# nosecone.net
KiCad netlist of a schematic drawn in EAGLE
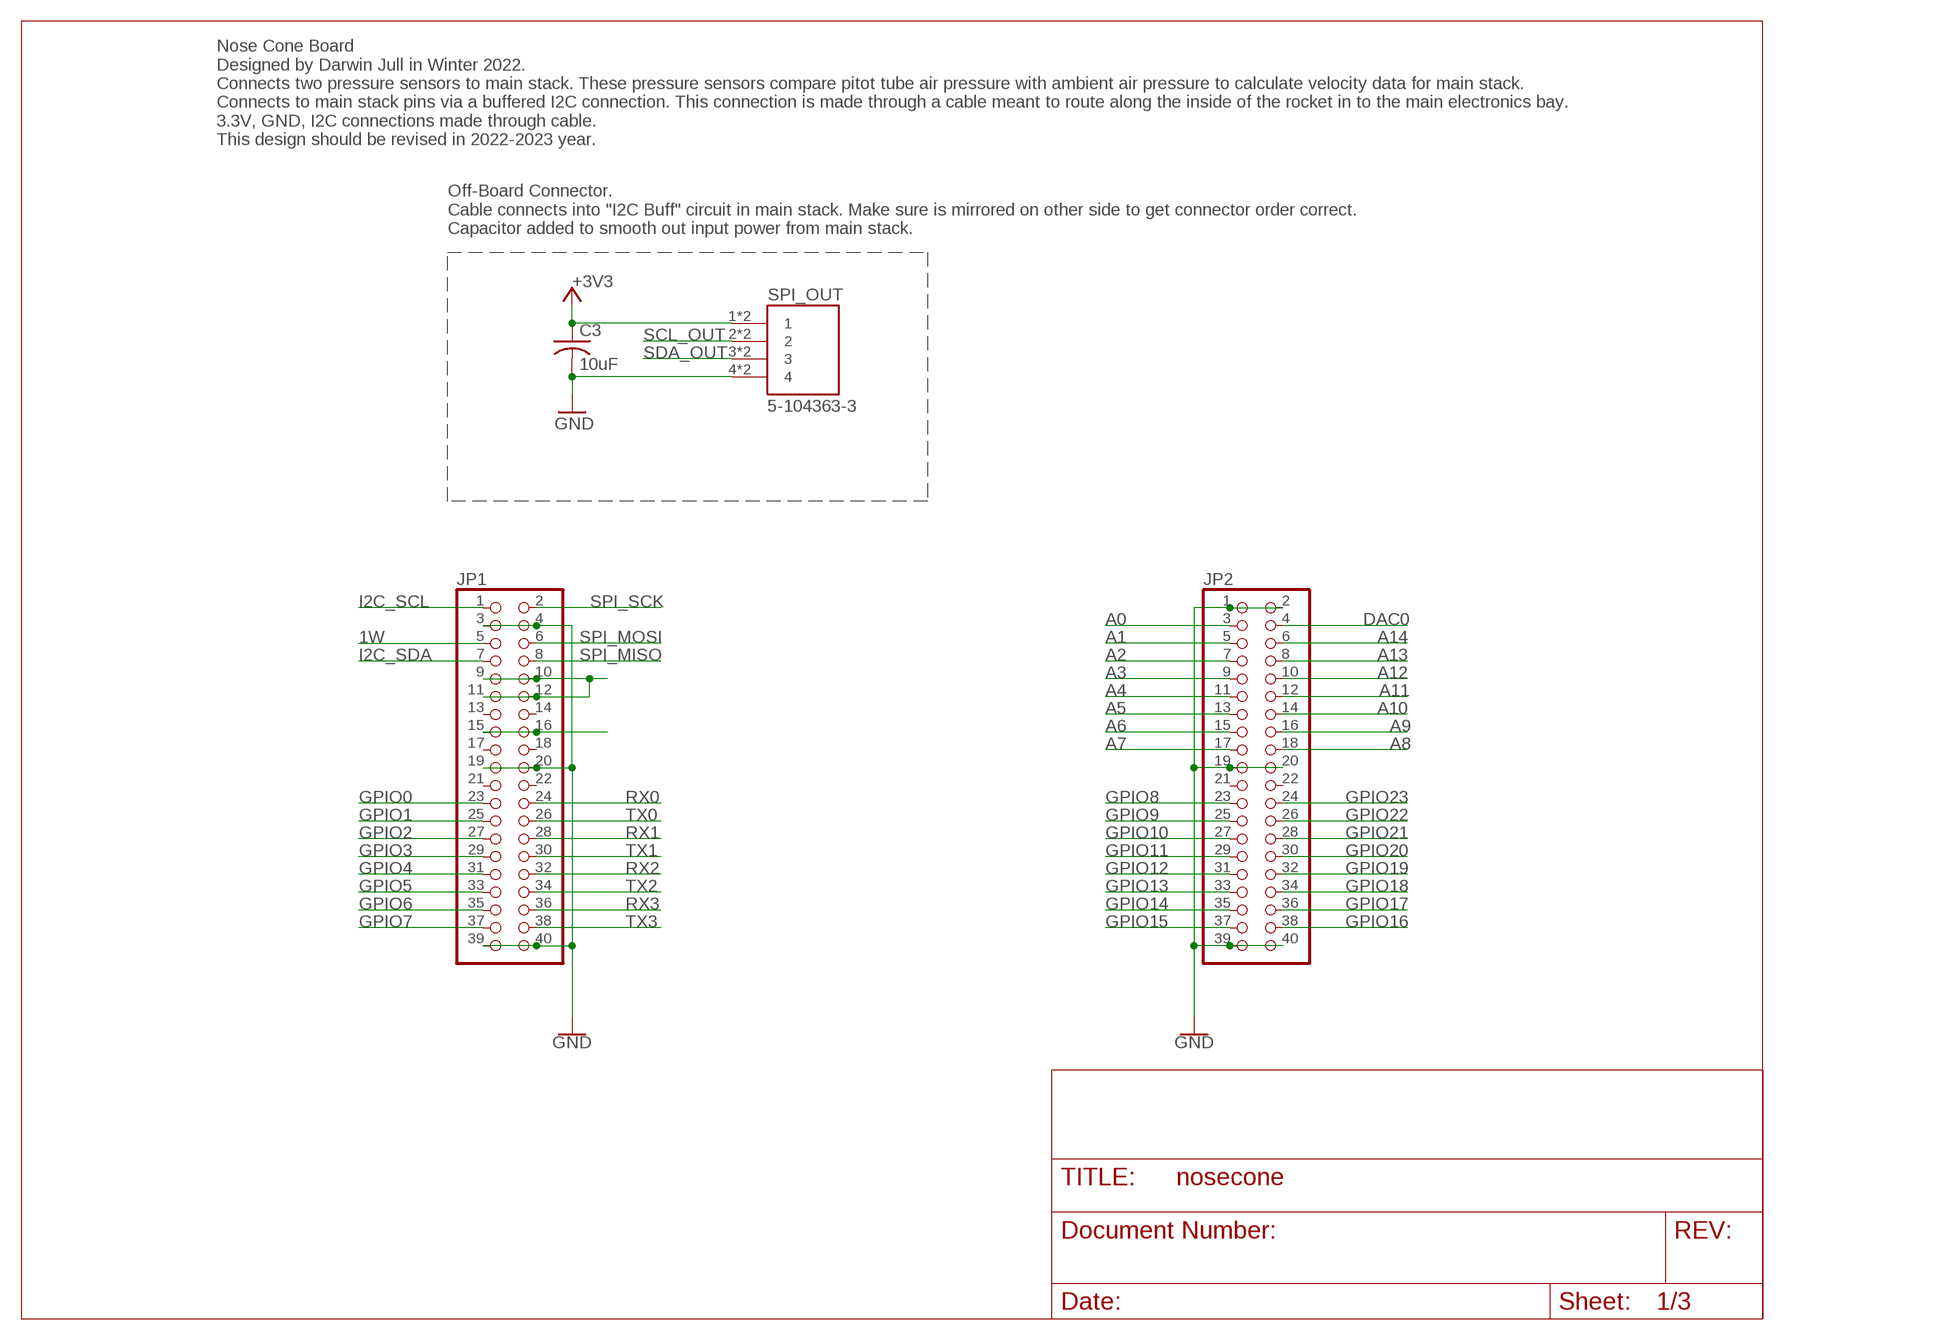
[diagram p0: schematic, sheet 1]
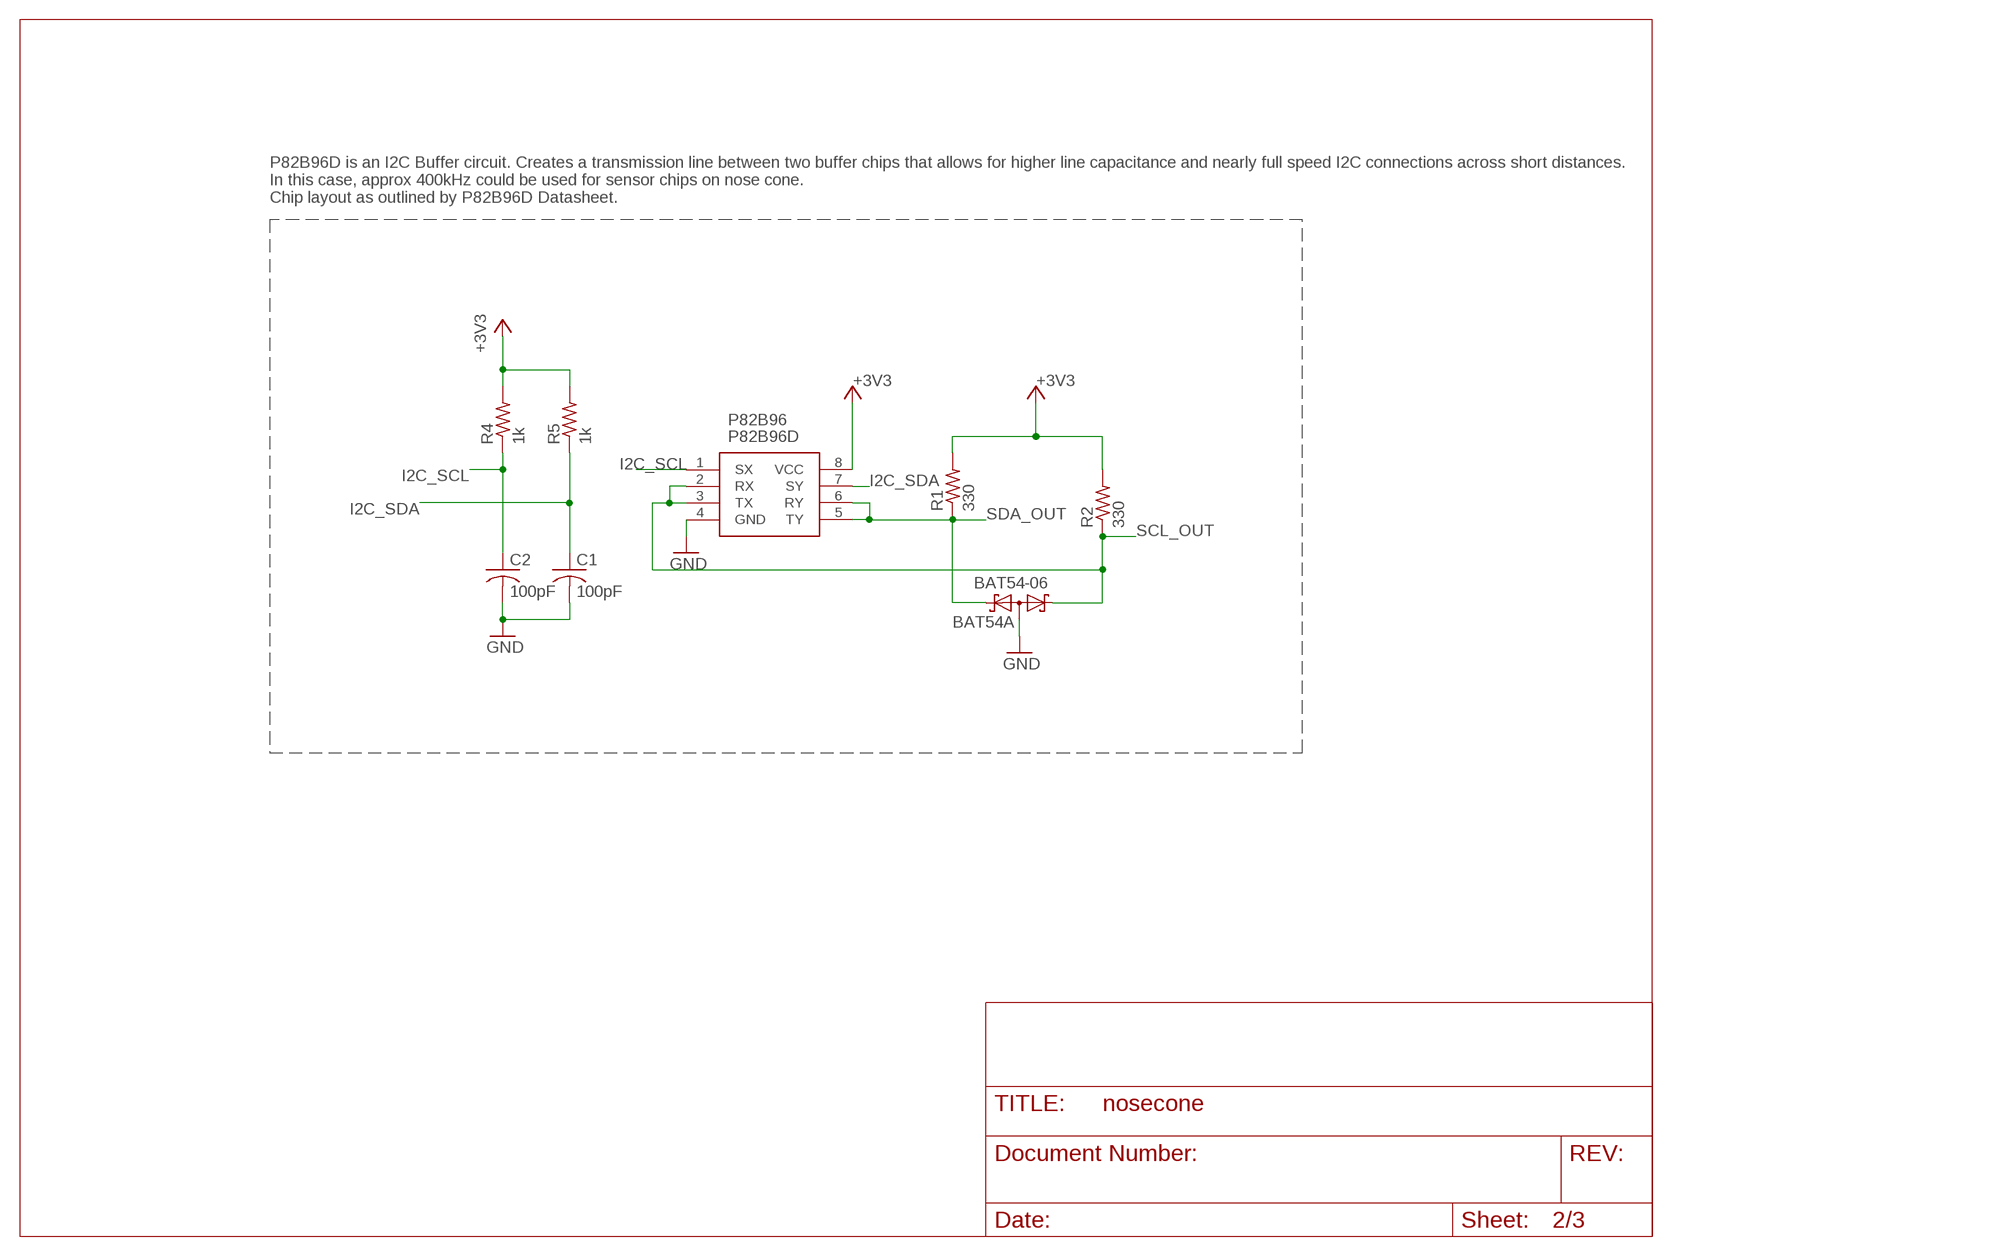
[diagram p1: schematic, sheet 2]
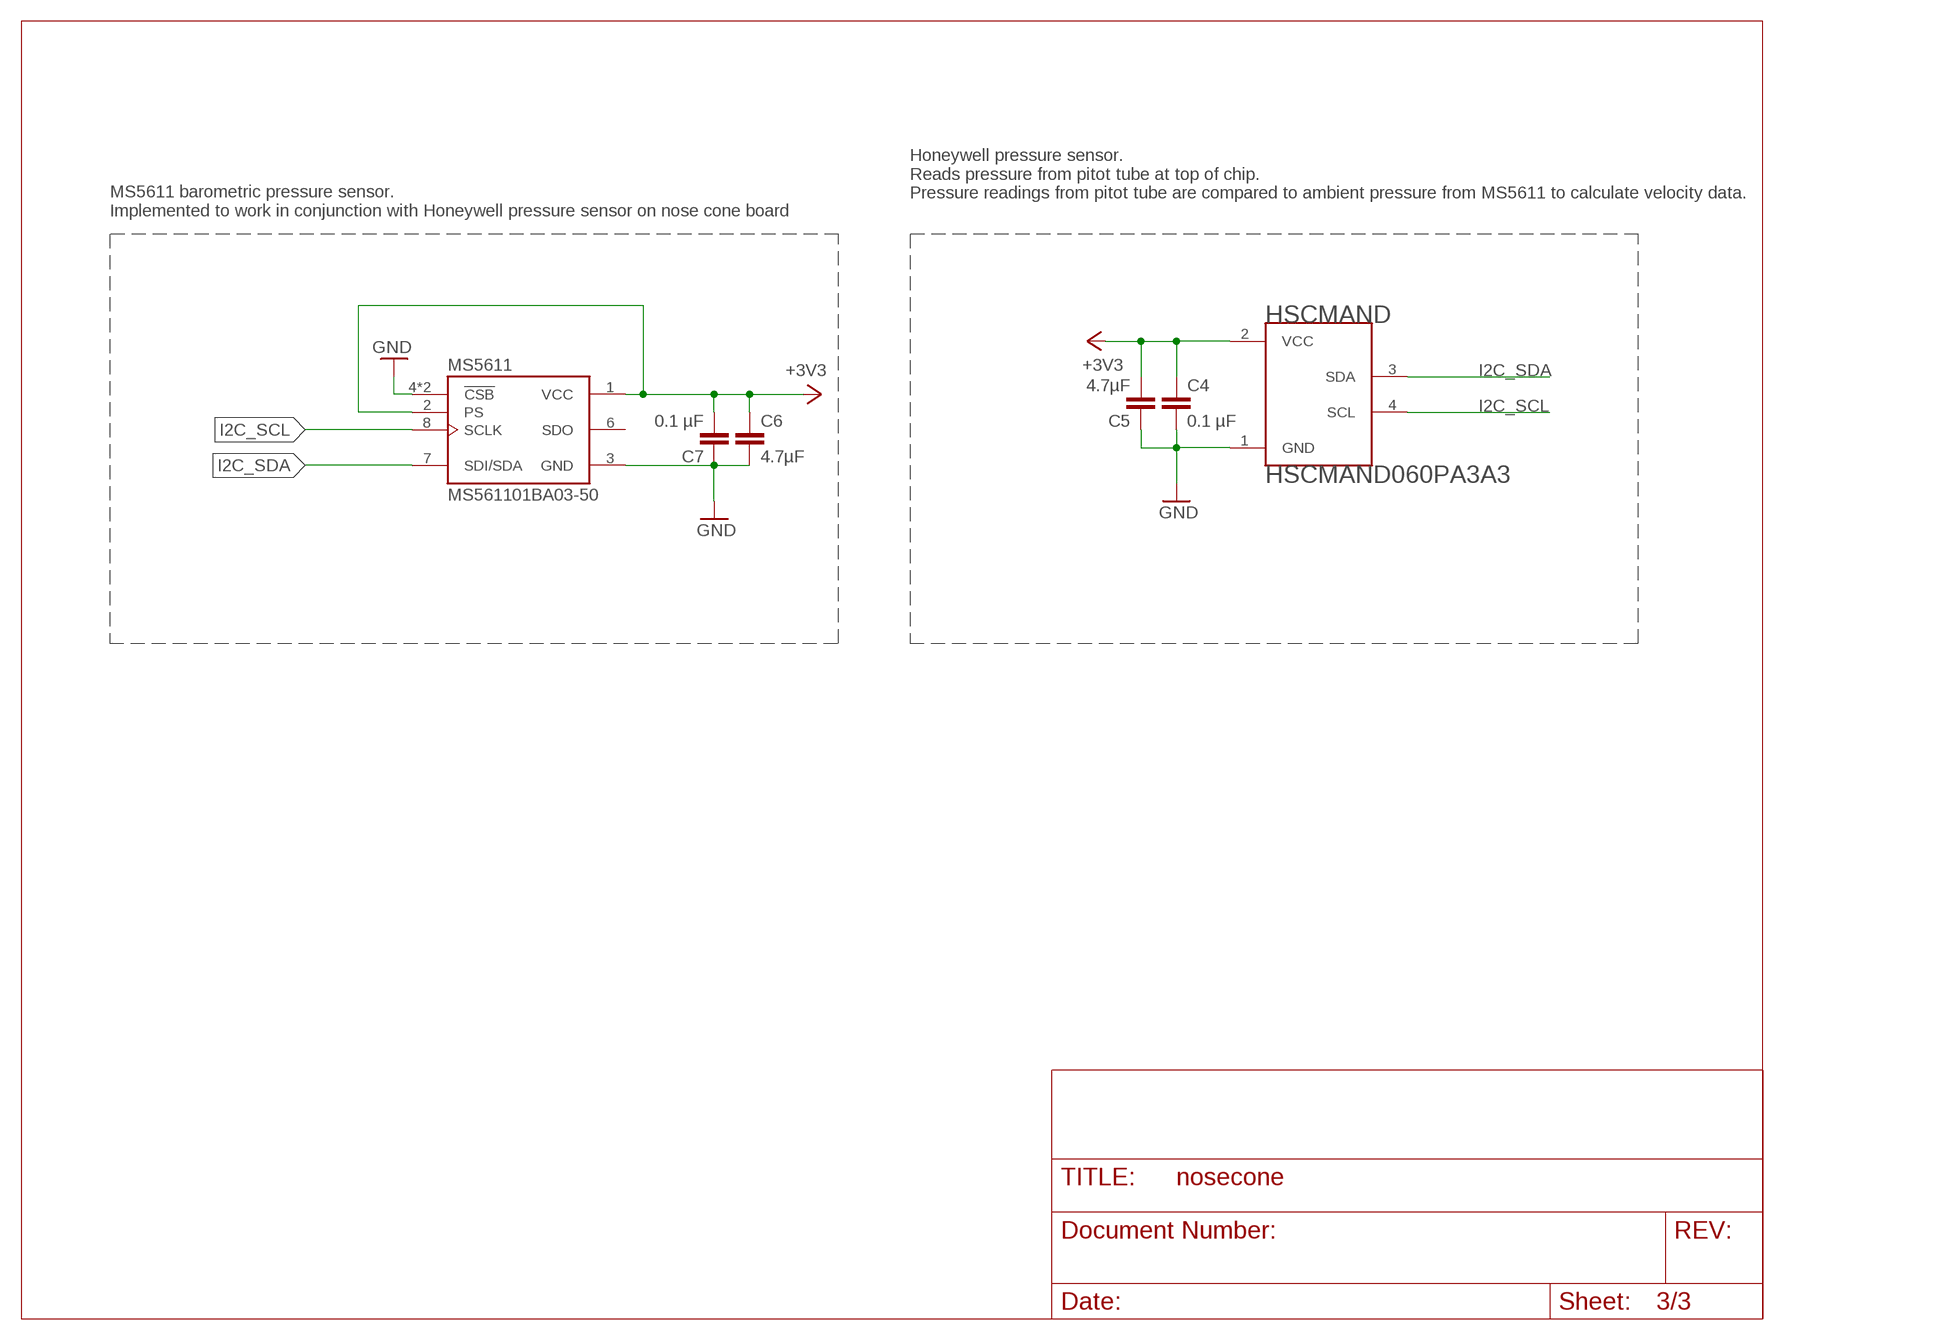
[diagram p2: schematic, sheet 3]

(export (version "E")
  (design (tool "Eeschema 10.0.6"))
  (components
    (comp (ref "C1")
      (value "100pF")
      (footprint "eagle-import:C0805")
      (libsource (lib "eagle-import") (part "C-USC0805"))
    )
    (comp (ref "C2")
      (value "100pF")
      (footprint "eagle-import:C0805")
      (libsource (lib "eagle-import") (part "C-USC0805"))
    )
    (comp (ref "D1")
      (value "BAT54-06")
      (footprint "eagle-import:SOT23")
      (libsource (lib "eagle-import") (part "BAT54-06"))
    )
    (comp (ref "P82B96")
      (value "P82B96D")
      (footprint "eagle-import:SOIC127P600X175-8N")
      (fields (field (name "MOUSER_PART_NUMBER") "595-P82B96D"))
      (libsource (lib "eagle-import") (part "P82B96D"))
    )
    (comp (ref "R1")
      (value "330")
      (footprint "eagle-import:R0805")
      (libsource (lib "eagle-import") (part "R-US_R0805"))
    )
    (comp (ref "R2")
      (value "330")
      (footprint "eagle-import:R0805")
      (libsource (lib "eagle-import") (part "R-US_R0805"))
    )
    (comp (ref "R4")
      (value "1k")
      (footprint "eagle-import:R0805")
      (libsource (lib "eagle-import") (part "R-US_R0805"))
    )
    (comp (ref "R5")
      (value "1k")
      (footprint "eagle-import:R0805")
      (libsource (lib "eagle-import") (part "R-US_R0805"))
    )
    (comp (ref "C3")
      (value "10uF")
      (footprint "eagle-import:C0805")
      (libsource (lib "eagle-import") (part "C-USC0805"))
    )
    (comp (ref "JP1")
      (value "PINHD-2X20")
      (footprint "eagle-import:2X20")
      (libsource (lib "eagle-import") (part "PINHD-2X20"))
    )
    (comp (ref "JP2")
      (value "PINHD-2X20")
      (footprint "eagle-import:2X20")
      (libsource (lib "eagle-import") (part "PINHD-2X20"))
    )
    (comp (ref "SPI_OUT")
      (value "5-104363-3")
      (footprint "eagle-import:TE_5-104363-3")
      (fields
        (field (name "DIGI-KEY_PART_NUMBER") "A32565-ND")
        (field (name "MF") "TE Connectivity")
        (field (name "MP") "51043633")
      )
      (libsource (lib "eagle-import") (part "5-104363-3"))
    )
    (comp (ref "C4")
      (value "0.1 µF")
      (footprint "eagle-import:C0805")
      (libsource (lib "eagle-import") (part "C-EUC0805"))
    )
    (comp (ref "C5")
      (value "4.7µF")
      (footprint "eagle-import:C0805")
      (libsource (lib "eagle-import") (part "C-EUC0805"))
    )
    (comp (ref "C6")
      (value "4.7µF")
      (footprint "eagle-import:C0805")
      (libsource (lib "eagle-import") (part "C-EUC0805"))
    )
    (comp (ref "C7")
      (value "0.1 µF")
      (footprint "eagle-import:C0805")
      (libsource (lib "eagle-import") (part "C-EUC0805"))
    )
    (comp (ref "HSCMAND")
      (value "HSCMAND060PA3A3")
      (footprint "eagle-import:HSC-SMT")
      (libsource (lib "eagle-import") (part "HSCMAND060PA3A3"))
    )
    (comp (ref "MS5611")
      (value "MS561101BA03-50")
      (footprint "eagle-import:SON125P500X300X100-8N")
      (fields (field (name "MF") "TE Connectivity"))
      (libsource (lib "eagle-import") (part "MS561101BA03-50"))
    )
  )
  (nets
    (net (code "1") (name "+3V3") (class "Default")
      (node (ref "C3") (pin "1") (pinfunction "1_1") (pintype "passive"))
      (node (ref "C4") (pin "1") (pinfunction "1_1") (pintype "passive"))
      (node (ref "C5") (pin "2") (pinfunction "2_2") (pintype "passive"))
      (node (ref "C6") (pin "1") (pinfunction "1_1") (pintype "passive"))
      (node (ref "C7") (pin "2") (pinfunction "2_2") (pintype "passive"))
      (node (ref "HSCMAND") (pin "2") (pinfunction "VCC_2") (pintype "bidirectional"))
      (node (ref "MS5611") (pin "1") (pinfunction "VCC_1") (pintype "power_in"))
      (node (ref "MS5611") (pin "2") (pinfunction "PS_2") (pintype "input"))
      (node (ref "P82B96") (pin "8") (pinfunction "VCC_8") (pintype "bidirectional"))
      (node (ref "R1") (pin "2") (pinfunction "2_2") (pintype "passive"))
      (node (ref "R2") (pin "2") (pinfunction "2_2") (pintype "passive"))
      (node (ref "R4") (pin "2") (pinfunction "2_2") (pintype "passive"))
      (node (ref "R5") (pin "2") (pinfunction "2_2") (pintype "passive"))
      (node (ref "SPI_OUT") (pin "1") (pinfunction "1_1") (pintype "passive"))
      (node (ref "SPI_OUT") (pin "1_1") (pinfunction "1_1_1") (pintype "passive"))
    )
    (net (code "2") (name "1W") (class "Default")
      (node (ref "JP1") (pin "5") (pinfunction "5_5") (pintype "passive"))
    )
    (net (code "3") (name "A0") (class "Default")
      (node (ref "JP2") (pin "3") (pinfunction "3_3") (pintype "passive"))
    )
    (net (code "4") (name "A1") (class "Default")
      (node (ref "JP2") (pin "5") (pinfunction "5_5") (pintype "passive"))
    )
    (net (code "5") (name "A2") (class "Default")
      (node (ref "JP2") (pin "7") (pinfunction "7_7") (pintype "passive"))
    )
    (net (code "6") (name "A3") (class "Default")
      (node (ref "JP2") (pin "9") (pinfunction "9_9") (pintype "passive"))
    )
    (net (code "7") (name "A4") (class "Default")
      (node (ref "JP2") (pin "11") (pinfunction "11_11") (pintype "passive"))
    )
    (net (code "8") (name "A5") (class "Default")
      (node (ref "JP2") (pin "13") (pinfunction "13_13") (pintype "passive"))
    )
    (net (code "9") (name "A6") (class "Default")
      (node (ref "JP2") (pin "15") (pinfunction "15_15") (pintype "passive"))
    )
    (net (code "10") (name "A7") (class "Default")
      (node (ref "JP2") (pin "17") (pinfunction "17_17") (pintype "passive"))
    )
    (net (code "11") (name "A8") (class "Default")
      (node (ref "JP2") (pin "18") (pinfunction "18_18") (pintype "passive"))
    )
    (net (code "12") (name "A9") (class "Default")
      (node (ref "JP2") (pin "16") (pinfunction "16_16") (pintype "passive"))
    )
    (net (code "13") (name "A10") (class "Default")
      (node (ref "JP2") (pin "14") (pinfunction "14_14") (pintype "passive"))
    )
    (net (code "14") (name "A11") (class "Default")
      (node (ref "JP2") (pin "12") (pinfunction "12_12") (pintype "passive"))
    )
    (net (code "15") (name "A12") (class "Default")
      (node (ref "JP2") (pin "10") (pinfunction "10_10") (pintype "passive"))
    )
    (net (code "16") (name "A13") (class "Default")
      (node (ref "JP2") (pin "8") (pinfunction "8_8") (pintype "passive"))
    )
    (net (code "17") (name "A14") (class "Default")
      (node (ref "JP2") (pin "6") (pinfunction "6_6") (pintype "passive"))
    )
    (net (code "18") (name "DAC0") (class "Default")
      (node (ref "JP2") (pin "4") (pinfunction "4_4") (pintype "passive"))
    )
    (net (code "19") (name "GND") (class "Default")
      (node (ref "C1") (pin "2") (pinfunction "2_2") (pintype "passive"))
      (node (ref "C2") (pin "2") (pinfunction "2_2") (pintype "passive"))
      (node (ref "C3") (pin "2") (pinfunction "2_2") (pintype "passive"))
      (node (ref "C4") (pin "2") (pinfunction "2_2") (pintype "passive"))
      (node (ref "C5") (pin "1") (pinfunction "1_1") (pintype "passive"))
      (node (ref "C6") (pin "2") (pinfunction "2_2") (pintype "passive"))
      (node (ref "C7") (pin "1") (pinfunction "1_1") (pintype "passive"))
      (node (ref "D1") (pin "3") (pinfunction "3_3") (pintype "passive"))
      (node (ref "HSCMAND") (pin "1") (pinfunction "GND_1") (pintype "bidirectional"))
      (node (ref "JP1") (pin "19") (pinfunction "19_19") (pintype "passive"))
      (node (ref "JP1") (pin "20") (pinfunction "20_20") (pintype "passive"))
      (node (ref "JP1") (pin "3") (pinfunction "3_3") (pintype "passive"))
      (node (ref "JP1") (pin "39") (pinfunction "39_39") (pintype "passive"))
      (node (ref "JP1") (pin "4") (pinfunction "4_4") (pintype "passive"))
      (node (ref "JP1") (pin "40") (pinfunction "40_40") (pintype "passive"))
      (node (ref "JP2") (pin "1") (pinfunction "1_1") (pintype "passive"))
      (node (ref "JP2") (pin "19") (pinfunction "19_19") (pintype "passive"))
      (node (ref "JP2") (pin "2") (pinfunction "2_2") (pintype "passive"))
      (node (ref "JP2") (pin "20") (pinfunction "20_20") (pintype "passive"))
      (node (ref "JP2") (pin "39") (pinfunction "39_39") (pintype "passive"))
      (node (ref "JP2") (pin "40") (pinfunction "40_40") (pintype "passive"))
      (node (ref "MS5611") (pin "3") (pinfunction "GND_3") (pintype "power_in"))
      (node (ref "MS5611") (pin "4") (pinfunction "~{CSB}_4") (pintype "input"))
      (node (ref "MS5611") (pin "5") (pinfunction "~{CSB}_5") (pintype "input"))
      (node (ref "P82B96") (pin "4") (pinfunction "GND_4") (pintype "bidirectional"))
      (node (ref "SPI_OUT") (pin "4") (pinfunction "4_4") (pintype "passive"))
      (node (ref "SPI_OUT") (pin "4_1") (pinfunction "4_4_1") (pintype "passive"))
    )
    (net (code "20") (name "GPIO0") (class "Default")
      (node (ref "JP1") (pin "23") (pinfunction "23_23") (pintype "passive"))
    )
    (net (code "21") (name "GPIO1") (class "Default")
      (node (ref "JP1") (pin "25") (pinfunction "25_25") (pintype "passive"))
    )
    (net (code "22") (name "GPIO2") (class "Default")
      (node (ref "JP1") (pin "27") (pinfunction "27_27") (pintype "passive"))
    )
    (net (code "23") (name "GPIO3") (class "Default")
      (node (ref "JP1") (pin "29") (pinfunction "29_29") (pintype "passive"))
    )
    (net (code "24") (name "GPIO4") (class "Default")
      (node (ref "JP1") (pin "31") (pinfunction "31_31") (pintype "passive"))
    )
    (net (code "25") (name "GPIO5") (class "Default")
      (node (ref "JP1") (pin "33") (pinfunction "33_33") (pintype "passive"))
    )
    (net (code "26") (name "GPIO6") (class "Default")
      (node (ref "JP1") (pin "35") (pinfunction "35_35") (pintype "passive"))
    )
    (net (code "27") (name "GPIO7") (class "Default")
      (node (ref "JP1") (pin "37") (pinfunction "37_37") (pintype "passive"))
    )
    (net (code "28") (name "GPIO8") (class "Default")
      (node (ref "JP2") (pin "23") (pinfunction "23_23") (pintype "passive"))
    )
    (net (code "29") (name "GPIO9") (class "Default")
      (node (ref "JP2") (pin "25") (pinfunction "25_25") (pintype "passive"))
    )
    (net (code "30") (name "GPIO10") (class "Default")
      (node (ref "JP2") (pin "27") (pinfunction "27_27") (pintype "passive"))
    )
    (net (code "31") (name "GPIO11") (class "Default")
      (node (ref "JP2") (pin "29") (pinfunction "29_29") (pintype "passive"))
    )
    (net (code "32") (name "GPIO12") (class "Default")
      (node (ref "JP2") (pin "31") (pinfunction "31_31") (pintype "passive"))
    )
    (net (code "33") (name "GPIO13") (class "Default")
      (node (ref "JP2") (pin "33") (pinfunction "33_33") (pintype "passive"))
    )
    (net (code "34") (name "GPIO14") (class "Default")
      (node (ref "JP2") (pin "35") (pinfunction "35_35") (pintype "passive"))
    )
    (net (code "35") (name "GPIO15") (class "Default")
      (node (ref "JP2") (pin "37") (pinfunction "37_37") (pintype "passive"))
    )
    (net (code "36") (name "GPIO16") (class "Default")
      (node (ref "JP2") (pin "38") (pinfunction "38_38") (pintype "passive"))
    )
    (net (code "37") (name "GPIO17") (class "Default")
      (node (ref "JP2") (pin "36") (pinfunction "36_36") (pintype "passive"))
    )
    (net (code "38") (name "GPIO18") (class "Default")
      (node (ref "JP2") (pin "34") (pinfunction "34_34") (pintype "passive"))
    )
    (net (code "39") (name "GPIO19") (class "Default")
      (node (ref "JP2") (pin "32") (pinfunction "32_32") (pintype "passive"))
    )
    (net (code "40") (name "GPIO20") (class "Default")
      (node (ref "JP2") (pin "30") (pinfunction "30_30") (pintype "passive"))
    )
    (net (code "41") (name "GPIO21") (class "Default")
      (node (ref "JP2") (pin "28") (pinfunction "28_28") (pintype "passive"))
    )
    (net (code "42") (name "GPIO22") (class "Default")
      (node (ref "JP2") (pin "26") (pinfunction "26_26") (pintype "passive"))
    )
    (net (code "43") (name "GPIO23") (class "Default")
      (node (ref "JP2") (pin "24") (pinfunction "24_24") (pintype "passive"))
    )
    (net (code "44") (name "I2C_SCL") (class "Default")
      (node (ref "C2") (pin "1") (pinfunction "1_1") (pintype "passive"))
      (node (ref "HSCMAND") (pin "4") (pinfunction "SCL_4") (pintype "bidirectional"))
      (node (ref "JP1") (pin "1") (pinfunction "1_1") (pintype "passive"))
      (node (ref "MS5611") (pin "8") (pinfunction "SCLK_8") (pintype "input"))
      (node (ref "P82B96") (pin "1") (pinfunction "SX_1") (pintype "bidirectional"))
      (node (ref "R4") (pin "1") (pinfunction "1_1") (pintype "passive"))
    )
    (net (code "45") (name "I2C_SDA") (class "Default")
      (node (ref "C1") (pin "1") (pinfunction "1_1") (pintype "passive"))
      (node (ref "HSCMAND") (pin "3") (pinfunction "SDA_3") (pintype "bidirectional"))
      (node (ref "JP1") (pin "7") (pinfunction "7_7") (pintype "passive"))
      (node (ref "MS5611") (pin "7") (pinfunction "SDI/SDA_7") (pintype "bidirectional"))
      (node (ref "P82B96") (pin "7") (pinfunction "SY_7") (pintype "bidirectional"))
      (node (ref "R5") (pin "1") (pinfunction "1_1") (pintype "passive"))
    )
    (net (code "46") (name "Net-(JP1-Pad10)") (class "Default")
      (node (ref "JP1") (pin "10") (pinfunction "10_10") (pintype "passive"))
      (node (ref "JP1") (pin "11") (pinfunction "11_11") (pintype "passive"))
      (node (ref "JP1") (pin "12") (pinfunction "12_12") (pintype "passive"))
      (node (ref "JP1") (pin "9") (pinfunction "9_9") (pintype "passive"))
    )
    (net (code "47") (name "Net-(JP1-Pad15)") (class "Default")
      (node (ref "JP1") (pin "15") (pinfunction "15_15") (pintype "passive"))
      (node (ref "JP1") (pin "16") (pinfunction "16_16") (pintype "passive"))
    )
    (net (code "48") (name "RX0") (class "Default")
      (node (ref "JP1") (pin "24") (pinfunction "24_24") (pintype "passive"))
    )
    (net (code "49") (name "RX1") (class "Default")
      (node (ref "JP1") (pin "28") (pinfunction "28_28") (pintype "passive"))
    )
    (net (code "50") (name "RX2") (class "Default")
      (node (ref "JP1") (pin "32") (pinfunction "32_32") (pintype "passive"))
    )
    (net (code "51") (name "RX3") (class "Default")
      (node (ref "JP1") (pin "36") (pinfunction "36_36") (pintype "passive"))
    )
    (net (code "52") (name "SCL_OUT") (class "Default")
      (node (ref "D1") (pin "1") (pinfunction "1_1") (pintype "passive"))
      (node (ref "P82B96") (pin "2") (pinfunction "RX_2") (pintype "bidirectional"))
      (node (ref "P82B96") (pin "3") (pinfunction "TX_3") (pintype "bidirectional"))
      (node (ref "R2") (pin "1") (pinfunction "1_1") (pintype "passive"))
      (node (ref "SPI_OUT") (pin "2") (pinfunction "2_2") (pintype "passive"))
      (node (ref "SPI_OUT") (pin "2_1") (pinfunction "2_2_1") (pintype "passive"))
    )
    (net (code "53") (name "SDA_OUT") (class "Default")
      (node (ref "D1") (pin "2") (pinfunction "2_2") (pintype "passive"))
      (node (ref "P82B96") (pin "5") (pinfunction "TY_5") (pintype "bidirectional"))
      (node (ref "P82B96") (pin "6") (pinfunction "RY_6") (pintype "bidirectional"))
      (node (ref "R1") (pin "1") (pinfunction "1_1") (pintype "passive"))
      (node (ref "SPI_OUT") (pin "3") (pinfunction "3_3") (pintype "passive"))
      (node (ref "SPI_OUT") (pin "3_1") (pinfunction "3_3_1") (pintype "passive"))
    )
    (net (code "54") (name "SPI_MISO") (class "Default")
      (node (ref "JP1") (pin "8") (pinfunction "8_8") (pintype "passive"))
    )
    (net (code "55") (name "SPI_MOSI") (class "Default")
      (node (ref "JP1") (pin "6") (pinfunction "6_6") (pintype "passive"))
    )
    (net (code "56") (name "SPI_SCK") (class "Default")
      (node (ref "JP1") (pin "2") (pinfunction "2_2") (pintype "passive"))
    )
    (net (code "57") (name "TX0") (class "Default")
      (node (ref "JP1") (pin "26") (pinfunction "26_26") (pintype "passive"))
    )
    (net (code "58") (name "TX1") (class "Default")
      (node (ref "JP1") (pin "30") (pinfunction "30_30") (pintype "passive"))
    )
    (net (code "59") (name "TX2") (class "Default")
      (node (ref "JP1") (pin "34") (pinfunction "34_34") (pintype "passive"))
    )
    (net (code "60") (name "TX3") (class "Default")
      (node (ref "JP1") (pin "38") (pinfunction "38_38") (pintype "passive"))
    )
    (net (code "61") (name "unconnected-(JP1-Pad13)") (class "Default")
      (node (ref "JP1") (pin "13") (pinfunction "13_13") (pintype "passive"))
    )
    (net (code "62") (name "unconnected-(JP1-Pad14)") (class "Default")
      (node (ref "JP1") (pin "14") (pinfunction "14_14") (pintype "passive"))
    )
    (net (code "63") (name "unconnected-(JP1-Pad17)") (class "Default")
      (node (ref "JP1") (pin "17") (pinfunction "17_17") (pintype "passive"))
    )
    (net (code "64") (name "unconnected-(JP1-Pad18)") (class "Default")
      (node (ref "JP1") (pin "18") (pinfunction "18_18") (pintype "passive"))
    )
    (net (code "65") (name "unconnected-(JP1-Pad21)") (class "Default")
      (node (ref "JP1") (pin "21") (pinfunction "21_21") (pintype "passive"))
    )
    (net (code "66") (name "unconnected-(JP1-Pad22)") (class "Default")
      (node (ref "JP1") (pin "22") (pinfunction "22_22") (pintype "passive"))
    )
    (net (code "67") (name "unconnected-(JP2-Pad21)") (class "Default")
      (node (ref "JP2") (pin "21") (pinfunction "21_21") (pintype "passive"))
    )
    (net (code "68") (name "unconnected-(JP2-Pad22)") (class "Default")
      (node (ref "JP2") (pin "22") (pinfunction "22_22") (pintype "passive"))
    )
    (net (code "69") (name "unconnected-(MS5611-SDO-Pad6)") (class "Default")
      (node (ref "MS5611") (pin "6") (pinfunction "SDO_6") (pintype "output"))
    )
  )
)
